# MiddleMotor_v1_0_2.net
KiCad netlist of a schematic drawn in EasyEDA Pro
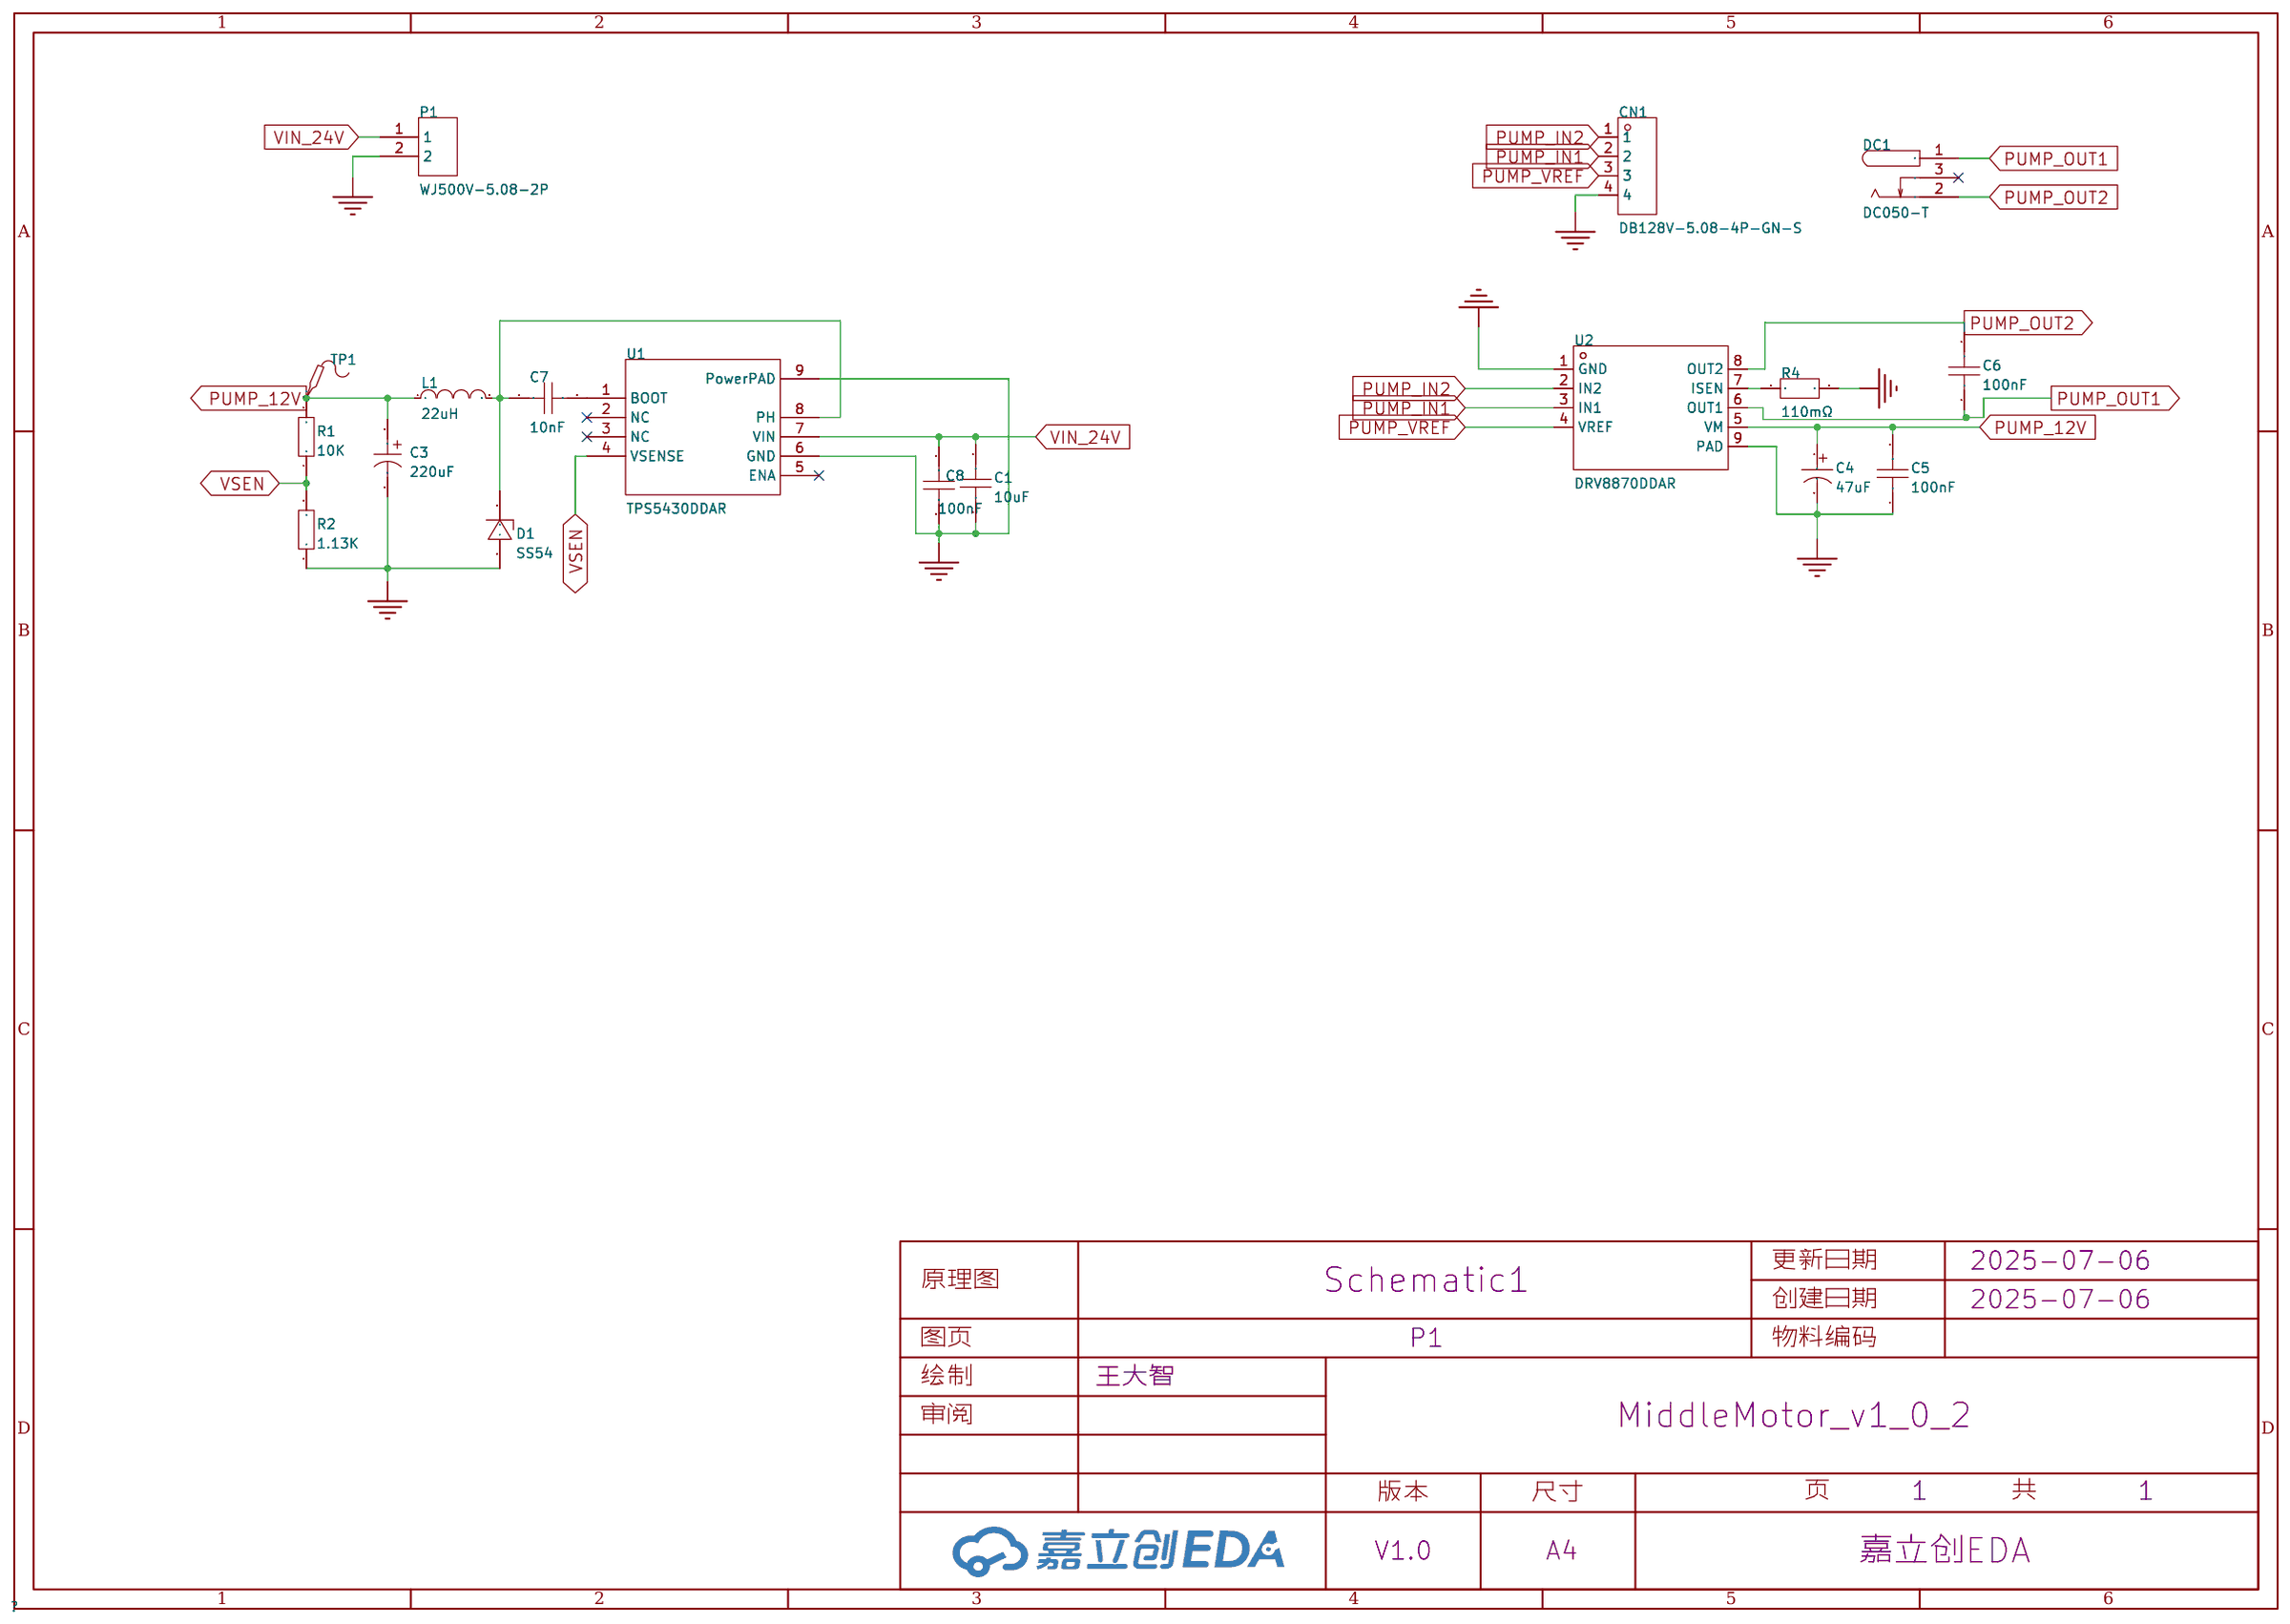
[diagram p0: schematic sheet]

(export (version "E")
  (design (tool "Eeschema 10.0.6"))
  (components
    (comp (ref "C1")
      (value "10uF")
      (footprint "easyedapro:C1206")
      (description "容值:10uF;精度:±10%;额定电压:50V;温度系数:X5R;")
      (fields
        (field (name "Manufacturer Part") "HGC1206R5106K500NSPJ")
        (field (name "Manufacturer") "Chinocera(华瓷)")
      )
      (libsource (lib "easyedapro") (part "HGC1206R5106K500NSPJ"))
    )
    (comp (ref "C3")
      (value "220uF")
      (footprint "easyedapro:CAP-SMD_BD8.0-L8.3-W8.3-FD")
      (description "容值:220uF;精度:±20%;额定电压:35V;纹波电流:175mA@120Hz;")
      (fields
        (field (name "Manufacturer Part") "GVT1V227M0810CNVC")
        (field (name "Manufacturer") "HRK(鸿瑞凯电子)")
      )
      (libsource (lib "easyedapro") (part "GVT1V227M0810CNVC"))
    )
    (comp (ref "C4")
      (value "47uF")
      (footprint "easyedapro:CAP-TH_BD6.3-P2.50-D1.0-FD")
      (description "容值:47uF;精度:±20%;额定电压:50V;")
      (fields
        (field (name "Manufacturer Part") "KM476M050E11RR0VH2FP0")
        (field (name "Manufacturer") "CX(承兴)")
      )
      (libsource (lib "easyedapro") (part "47uF 50V 6.3*11_C45101"))
    )
    (comp (ref "C5")
      (value "100nF")
      (footprint "easyedapro:C0603")
      (description "容值:100nF;精度:±10%;额定电压:50V;温度系数:X7R;")
      (fields
        (field (name "Manufacturer Part") "CGA0603X7R104K500JT")
        (field (name "Manufacturer") "HRE(芯声)")
      )
      (libsource (lib "easyedapro") (part "CGA0603X7R104K500JT"))
    )
    (comp (ref "C6")
      (value "100nF")
      (footprint "easyedapro:C0603")
      (description "容值:100nF;精度:±10%;额定电压:50V;温度系数:X7R;")
      (fields
        (field (name "Manufacturer Part") "CGA0603X7R104K500JT")
        (field (name "Manufacturer") "HRE(芯声)")
      )
      (libsource (lib "easyedapro") (part "CGA0603X7R104K500JT"))
    )
    (comp (ref "C7")
      (value "10nF")
      (footprint "easyedapro:C0603")
      (libsource (lib "easyedapro") (part "CapAcitance"))
    )
    (comp (ref "C8")
      (value "100nF")
      (footprint "easyedapro:C0603")
      (libsource (lib "easyedapro") (part "CapAcitance"))
    )
    (comp (ref "CN1")
      (value "DB128V-5.08-4P-GN-S")
      (footprint "easyedapro:CONN-TH_4P-P5.08_DIBO_DB128V-5.08")
      (fields (field (name "Manufacturer") "DORABO(地博电气)"))
      (libsource (lib "easyedapro") (part "DB128V-5.08-4P-GN-S"))
    )
    (comp (ref "D1")
      (value "SS54")
      (footprint "easyedapro:SMA_L4.3-W2.6-LS5.0-FD")
      (description "二极管配置:独立式;正向压降(Vf):550mV@5.0A;直流反向耐压(Vr):40V;整流电流:5A;")
      (fields (field (name "Manufacturer") "宏迦橙"))
      (libsource (lib "easyedapro") (part "SS54_C7420369"))
    )
    (comp (ref "DC1")
      (value "DC050-T")
      (footprint "easyedapro:DC-IN_DC050-T")
      (description "连接器类型:DC电源插座;安装方式:卧贴;触点内径:2mm;触点外径:6.4mm;额定电流:2A;额定电压:30V;工作温度范围:-25°C~+70°C;")
      (fields (field (name "Manufacturer") "SHOU HAN(首韩)"))
      (libsource (lib "easyedapro") (part "DC050-T"))
    )
    (comp (ref "L1")
      (value "22uH")
      (footprint "easyedapro:IND-SMD_L7.0-W6.6_FXL0630")
      (description "电感值:22uH;精度:±20%;额定电流:2.5A;饱和电流(Isat):3A;类型:一体成型电感;")
      (fields (field (name "Manufacturer Part") "FXL0630-220-M") (field (name "Manufacturer") "cjiang(长江微电)"))
      (libsource (lib "easyedapro") (part "FXL0630-220-M"))
    )
    (comp (ref "P1")
      (value "WJ500V-5.08-2P")
      (footprint "easyedapro:CONN-TH_2P-P5.00_WJ500V-5.08-2P")
      (fields (field (name "Manufacturer") "KANGNEX(康奈克斯电气)"))
      (libsource (lib "easyedapro") (part "WJ500V-5.08-2P-14-00A"))
    )
    (comp (ref "R1") (value "10K") (footprint "easyedapro:R0603") (libsource (lib "easyedapro") (part "电阻")))
    (comp (ref "R2")
      (value "1.13K")
      (footprint "easyedapro:R0603")
      (libsource (lib "easyedapro") (part "电阻"))
    )
    (comp (ref "R4")
      (value "110mΩ")
      (footprint "easyedapro:R1206")
      (description "电阻类型:厚膜电阻;阻值:110mΩ;精度:±1%;功率:250mW;最大工作电压:500V;温度系数:±600ppm/°C;")
      (fields (field (name "Manufacturer Part") "FRL1206FR110TS") (field (name "Manufacturer") "FOJAN(富捷)"))
      (libsource (lib "easyedapro") (part "FRL1206FR110TS"))
    )
    (comp (ref "TP1")
      (value "~")
      (footprint "easyedapro:Test-Point-0.5mm")
      (description "Test Point 测试点")
      (libsource (lib "easyedapro") (part "Test-Point"))
    )
    (comp (ref "U1")
      (value "TPS5430DDAR")
      (footprint "easyedapro:ESOP-8_L4.9-W3.9-P1.27-LS6.0-TL-EP")
      (description "功能类型:降压型;输出类型:可调;工作电压:5.5V~36V;输出电压:1.221V~32.04V;输出电流:3A;")
      (fields (field (name "Manufacturer") "TI(德州仪器)"))
      (libsource (lib "easyedapro") (part "TPS5430DDAR"))
    )
    (comp (ref "U2")
      (value "DRV8870DDAR")
      (footprint "easyedapro:HSOP-8_L5.0-W4.0-P1.27-LS6.2-BL-EP")
      (description "DRV8870 具有电流调节功能的 50V、3.6A、H 桥电机驱动器")
      (fields (field (name "Manufacturer") "TI(德州仪器)"))
      (libsource (lib "easyedapro") (part "DRV8870DDAR"))
    )
  )
  (nets
    (net (code "1") (name "GND") (class "Default")
      (node (ref "C1") (pin "1") (pinfunction "1_1") (pintype "unspecified"))
      (node (ref "C3") (pin "2") (pinfunction "2_2") (pintype "input"))
      (node (ref "C4") (pin "2") (pinfunction "2_2") (pintype "input"))
      (node (ref "C5") (pin "1") (pinfunction "1_1") (pintype "unspecified"))
      (node (ref "C8") (pin "2") (pinfunction "2_2") (pintype "input"))
      (node (ref "CN1") (pin "4") (pinfunction "4_4") (pintype "unspecified"))
      (node (ref "D1") (pin "1") (pinfunction "A_1") (pintype "unspecified"))
      (node (ref "P1") (pin "2") (pinfunction "2_2") (pintype "unspecified"))
      (node (ref "R2") (pin "1") (pinfunction "1_1") (pintype "input"))
      (node (ref "R4") (pin "2") (pinfunction "2_2") (pintype "unspecified"))
      (node (ref "U1") (pin "6") (pinfunction "GND_6") (pintype "unspecified"))
      (node (ref "U1") (pin "9") (pinfunction "PowerPAD_9") (pintype "unspecified"))
      (node (ref "U2") (pin "1") (pinfunction "GND_1") (pintype "unspecified"))
      (node (ref "U2") (pin "9") (pinfunction "PAD_9") (pintype "unspecified"))
    )
    (net (code "2") (name "Net-(D1-K)") (class "Default")
      (node (ref "C7") (pin "1") (pinfunction "1_1") (pintype "input"))
      (node (ref "D1") (pin "2") (pinfunction "K_2") (pintype "unspecified"))
      (node (ref "L1") (pin "2") (pinfunction "2_2") (pintype "unspecified"))
      (node (ref "U1") (pin "8") (pinfunction "PH_8") (pintype "unspecified"))
    )
    (net (code "3") (name "Net-(U1-BOOT)") (class "Default")
      (node (ref "C7") (pin "2") (pinfunction "2_2") (pintype "input"))
      (node (ref "U1") (pin "1") (pinfunction "BOOT_1") (pintype "unspecified"))
    )
    (net (code "4") (name "Net-(U2-ISEN)") (class "Default")
      (node (ref "R4") (pin "1") (pinfunction "1_1") (pintype "unspecified"))
      (node (ref "U2") (pin "7") (pinfunction "ISEN_7") (pintype "unspecified"))
    )
    (net (code "5") (name "PUMP_12V") (class "Default")
      (node (ref "C3") (pin "1") (pinfunction "1_1") (pintype "input"))
      (node (ref "C4") (pin "1") (pinfunction "1_1") (pintype "input"))
      (node (ref "C5") (pin "2") (pinfunction "2_2") (pintype "unspecified"))
      (node (ref "L1") (pin "1") (pinfunction "1_1") (pintype "unspecified"))
      (node (ref "R1") (pin "2") (pinfunction "2_2") (pintype "input"))
      (node (ref "TP1") (pin "1") (pinfunction "1_1") (pintype "input"))
      (node (ref "U2") (pin "5") (pinfunction "VM_5") (pintype "unspecified"))
    )
    (net (code "6") (name "PUMP_IN1") (class "Default")
      (node (ref "CN1") (pin "2") (pinfunction "2_2") (pintype "unspecified"))
      (node (ref "U2") (pin "3") (pinfunction "IN1_3") (pintype "unspecified"))
    )
    (net (code "7") (name "PUMP_IN2") (class "Default")
      (node (ref "CN1") (pin "1") (pinfunction "1_1") (pintype "unspecified"))
      (node (ref "U2") (pin "2") (pinfunction "IN2_2") (pintype "unspecified"))
    )
    (net (code "8") (name "PUMP_OUT1") (class "Default")
      (node (ref "C6") (pin "1") (pinfunction "1_1") (pintype "unspecified"))
      (node (ref "DC1") (pin "1") (pinfunction "1_1") (pintype "unspecified"))
      (node (ref "U2") (pin "6") (pinfunction "OUT1_6") (pintype "unspecified"))
    )
    (net (code "9") (name "PUMP_OUT2") (class "Default")
      (node (ref "C6") (pin "2") (pinfunction "2_2") (pintype "unspecified"))
      (node (ref "DC1") (pin "2") (pinfunction "2_2") (pintype "unspecified"))
      (node (ref "U2") (pin "8") (pinfunction "OUT2_8") (pintype "unspecified"))
    )
    (net (code "10") (name "PUMP_VREF") (class "Default")
      (node (ref "CN1") (pin "3") (pinfunction "3_3") (pintype "unspecified"))
      (node (ref "U2") (pin "4") (pinfunction "VREF_4") (pintype "unspecified"))
    )
    (net (code "11") (name "VIN_24V") (class "Default")
      (node (ref "C1") (pin "2") (pinfunction "2_2") (pintype "unspecified"))
      (node (ref "C8") (pin "1") (pinfunction "1_1") (pintype "input"))
      (node (ref "P1") (pin "1") (pinfunction "1_1") (pintype "unspecified"))
      (node (ref "U1") (pin "7") (pinfunction "VIN_7") (pintype "unspecified"))
    )
    (net (code "12") (name "VSEN") (class "Default")
      (node (ref "R1") (pin "1") (pinfunction "1_1") (pintype "input"))
      (node (ref "R2") (pin "2") (pinfunction "2_2") (pintype "input"))
      (node (ref "U1") (pin "4") (pinfunction "VSENSE_4") (pintype "unspecified"))
    )
    (net (code "13") (name "unconnected-(DC1-Pad3)") (class "Default")
      (node (ref "DC1") (pin "3") (pinfunction "3_3") (pintype "unspecified+no_connect"))
    )
    (net (code "14") (name "unconnected-(U1-ENA-Pad5)") (class "Default")
      (node (ref "U1") (pin "5") (pinfunction "ENA_5") (pintype "unspecified+no_connect"))
    )
    (net (code "15") (name "unconnected-(U1-NC-Pad2)") (class "Default")
      (node (ref "U1") (pin "2") (pinfunction "NC_2") (pintype "unspecified+no_connect"))
    )
    (net (code "16") (name "unconnected-(U1-NC-Pad3)") (class "Default")
      (node (ref "U1") (pin "3") (pinfunction "NC_3") (pintype "unspecified+no_connect"))
    )
  )
)
